# LB_BIT_o5_DCMOTOR-v03_rev1.net
KiCad netlist of a schematic drawn in EAGLE
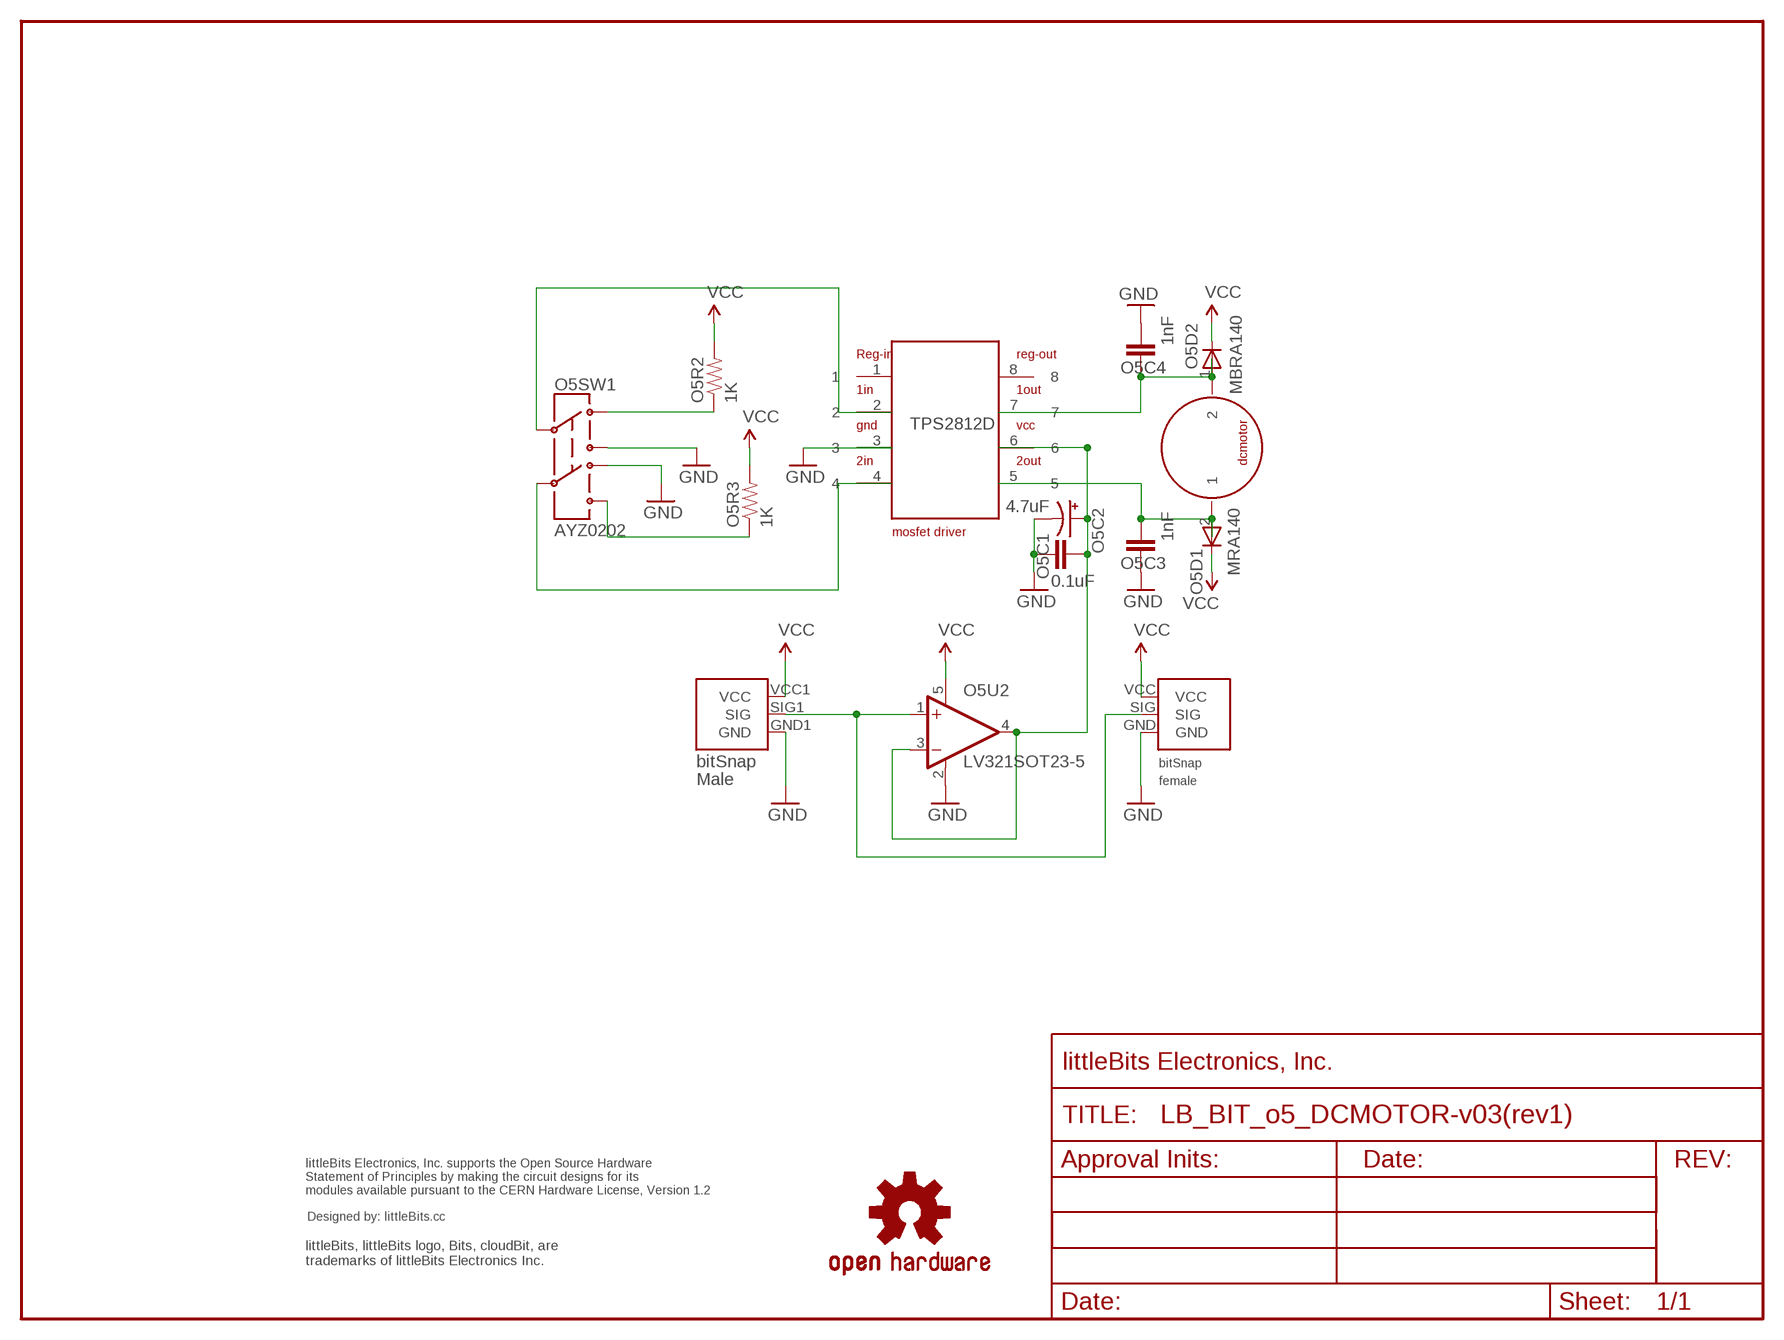
[diagram p0: schematic, sheet 1]

(export (version "E")
  (design (tool "Eeschema 10.0.6"))
  (components
    (comp (ref "O5BSF1")
      (value "BITSNAP_V03_FEMALE")
      (footprint "eagle-import:BITSNAP_V03_FEMALE")
      (libsource (lib "eagle-import") (part "BITSNAP_V03_FEMALE"))
    )
    (comp (ref "O5BSM1")
      (value "BITSNAP_V03_MALE")
      (footprint "eagle-import:BITSNAP_V03_MALE")
      (libsource (lib "eagle-import") (part "BITSNAP_V03_MALE"))
    )
    (comp (ref "O5C1")
      (value "0.1uF")
      (footprint "eagle-import:0603-CAP")
      (libsource (lib "eagle-import") (part "CAP0603-CAP"))
    )
    (comp (ref "O5C2")
      (value "4.7uF")
      (footprint "eagle-import:EIA3216")
      (libsource (lib "eagle-import") (part "CAP_POL1206"))
    )
    (comp (ref "O5C3")
      (value "1nF")
      (footprint "eagle-import:0603-CAP")
      (libsource (lib "eagle-import") (part "CAP0603-CAP"))
    )
    (comp (ref "O5C4")
      (value "1nF")
      (footprint "eagle-import:0603-CAP")
      (libsource (lib "eagle-import") (part "CAP0603-CAP"))
    )
    (comp (ref "O5D1")
      (value "MRA140")
      (footprint "eagle-import:SMA-DIODE")
      (libsource (lib "eagle-import") (part "DIODESMA"))
    )
    (comp (ref "O5D2")
      (value "MBRA140")
      (footprint "eagle-import:SMA-DIODE")
      (libsource (lib "eagle-import") (part "DIODESMA"))
    )
    (comp (ref "O5M1")
      (value "MOTOR-DC-GEARED")
      (footprint "eagle-import:MOTOR-GEARED")
      (libsource (lib "eagle-import") (part "MOTOR-DC-GEARED"))
    )
    (comp (ref "O5R2")
      (value "1K")
      (footprint "eagle-import:0603-RES")
      (libsource (lib "eagle-import") (part "RESISTOR0603-RES"))
    )
    (comp (ref "O5R3")
      (value "1K")
      (footprint "eagle-import:0603-RES")
      (libsource (lib "eagle-import") (part "RESISTOR0603-RES"))
    )
    (comp (ref "O5SW1")
      (value "AYZ0202")
      (footprint "eagle-import:AYZ0202")
      (libsource (lib "eagle-import") (part "AYZ0202"))
    )
    (comp (ref "O5U1")
      (value "TPS2812-SOIC8")
      (footprint "eagle-import:TPS2812")
      (libsource (lib "eagle-import") (part "TPS2812-SOIC8"))
    )
    (comp (ref "O5U2")
      (value "LV321SOT23-5")
      (footprint "eagle-import:SOT23-5")
      (libsource (lib "eagle-import") (part "LV321SOT23-5"))
    )
    (comp (ref "U$1")
      (value "OSHWCREDIT")
      (footprint "eagle-import:OSHWCREDIT")
      (libsource (lib "eagle-import") (part "OSHWCREDIT"))
    )
    (comp (ref "U$2")
      (value "FRAME-LETTER-OHWOHW")
      (footprint "eagle-import:FABDWG01-OHW")
      (libsource (lib "eagle-import") (part "FRAME-LETTER-OHWOHW"))
    )
    (comp (ref "U$4")
      (value "OSHW-LOGOL")
      (footprint "eagle-import:OSHW-LOGO-L")
      (libsource (lib "eagle-import") (part "OSHW-LOGOL"))
    )
  )
  (nets
    (net (code "1") (name "GND") (class "Default")
      (node (ref "O5BSF1") (pin "GND") (pinfunction "GND_GND") (pintype "bidirectional"))
      (node (ref "O5BSM1") (pin "GND1") (pinfunction "GND_GND1") (pintype "bidirectional"))
      (node (ref "O5C1") (pin "1") (pinfunction "1_1") (pintype "passive"))
      (node (ref "O5C2") (pin "C") (pinfunction "-_C") (pintype "passive"))
      (node (ref "O5C3") (pin "1") (pinfunction "1_1") (pintype "passive"))
      (node (ref "O5C4") (pin "2") (pinfunction "2_2") (pintype "passive"))
      (node (ref "O5SW1") (pin "1") (pinfunction "3_1") (pintype "bidirectional"))
      (node (ref "O5SW1") (pin "6") (pinfunction "4_6") (pintype "bidirectional"))
      (node (ref "O5U1") (pin "3") (pinfunction "3_3") (pintype "bidirectional"))
      (node (ref "O5U2") (pin "2") (pinfunction "V-_2") (pintype "power_in"))
    )
    (net (code "2") (name "Net-(O5BSM1-SIG)") (class "Default")
      (node (ref "O5BSF1") (pin "SIG") (pinfunction "SIG_SIG") (pintype "bidirectional"))
      (node (ref "O5BSM1") (pin "SIG1") (pinfunction "SIG_SIG1") (pintype "bidirectional"))
      (node (ref "O5U2") (pin "1") (pinfunction "+IN_1") (pintype "input"))
    )
    (net (code "3") (name "Net-(O5C2-+)") (class "Default")
      (node (ref "O5C1") (pin "2") (pinfunction "2_2") (pintype "passive"))
      (node (ref "O5C2") (pin "A") (pinfunction "+_A") (pintype "passive"))
      (node (ref "O5U1") (pin "6") (pinfunction "6_6") (pintype "bidirectional"))
      (node (ref "O5U2") (pin "3") (pinfunction "-IN_3") (pintype "input"))
      (node (ref "O5U2") (pin "4") (pinfunction "OUT_4") (pintype "output"))
    )
    (net (code "4") (name "Net-(O5M1-1)") (class "Default")
      (node (ref "O5C3") (pin "2") (pinfunction "2_2") (pintype "passive"))
      (node (ref "O5D1") (pin "A") (pinfunction "A_A") (pintype "passive"))
      (node (ref "O5M1") (pin "2") (pinfunction "1_2") (pintype "bidirectional"))
      (node (ref "O5U1") (pin "5") (pinfunction "5_5") (pintype "bidirectional"))
    )
    (net (code "5") (name "Net-(O5M1-2)") (class "Default")
      (node (ref "O5C4") (pin "1") (pinfunction "1_1") (pintype "passive"))
      (node (ref "O5D2") (pin "A") (pinfunction "A_A") (pintype "passive"))
      (node (ref "O5M1") (pin "1") (pinfunction "2_1") (pintype "bidirectional"))
      (node (ref "O5U1") (pin "7") (pinfunction "7_7") (pintype "bidirectional"))
    )
    (net (code "6") (name "Net-(O5SW1-1)") (class "Default")
      (node (ref "O5R2") (pin "1") (pinfunction "1_1") (pintype "passive"))
      (node (ref "O5SW1") (pin "3") (pinfunction "1_3") (pintype "bidirectional"))
    )
    (net (code "7") (name "Net-(O5SW1-6)") (class "Default")
      (node (ref "O5R3") (pin "1") (pinfunction "1_1") (pintype "passive"))
      (node (ref "O5SW1") (pin "4") (pinfunction "6_4") (pintype "bidirectional"))
    )
    (net (code "8") (name "Net-(O5SW1-Pad2)") (class "Default")
      (node (ref "O5SW1") (pin "2") (pinfunction "2_2") (pintype "bidirectional"))
      (node (ref "O5U1") (pin "2") (pinfunction "2_2") (pintype "bidirectional"))
    )
    (net (code "9") (name "Net-(O5SW1-Pad5)") (class "Default")
      (node (ref "O5SW1") (pin "5") (pinfunction "5_5") (pintype "bidirectional"))
      (node (ref "O5U1") (pin "4") (pinfunction "4_4") (pintype "bidirectional"))
    )
    (net (code "10") (name "VCC") (class "Default")
      (node (ref "O5BSF1") (pin "VCC") (pinfunction "VCC_VCC") (pintype "bidirectional"))
      (node (ref "O5BSM1") (pin "VCC1") (pinfunction "VCC_VCC1") (pintype "bidirectional"))
      (node (ref "O5D1") (pin "C") (pinfunction "C_C") (pintype "passive"))
      (node (ref "O5D2") (pin "C") (pinfunction "C_C") (pintype "passive"))
      (node (ref "O5R2") (pin "2") (pinfunction "2_2") (pintype "passive"))
      (node (ref "O5R3") (pin "2") (pinfunction "2_2") (pintype "passive"))
      (node (ref "O5U2") (pin "5") (pinfunction "V+_5") (pintype "power_in"))
    )
    (net (code "11") (name "unconnected-(O5U1-Pad1)") (class "Default")
      (node (ref "O5U1") (pin "1") (pinfunction "1_1") (pintype "bidirectional"))
    )
    (net (code "12") (name "unconnected-(O5U1-Pad8)") (class "Default")
      (node (ref "O5U1") (pin "8") (pinfunction "8_8") (pintype "bidirectional"))
    )
  )
)
